# sc16is752.net
KiCad netlist of a schematic drawn in Altium Designer
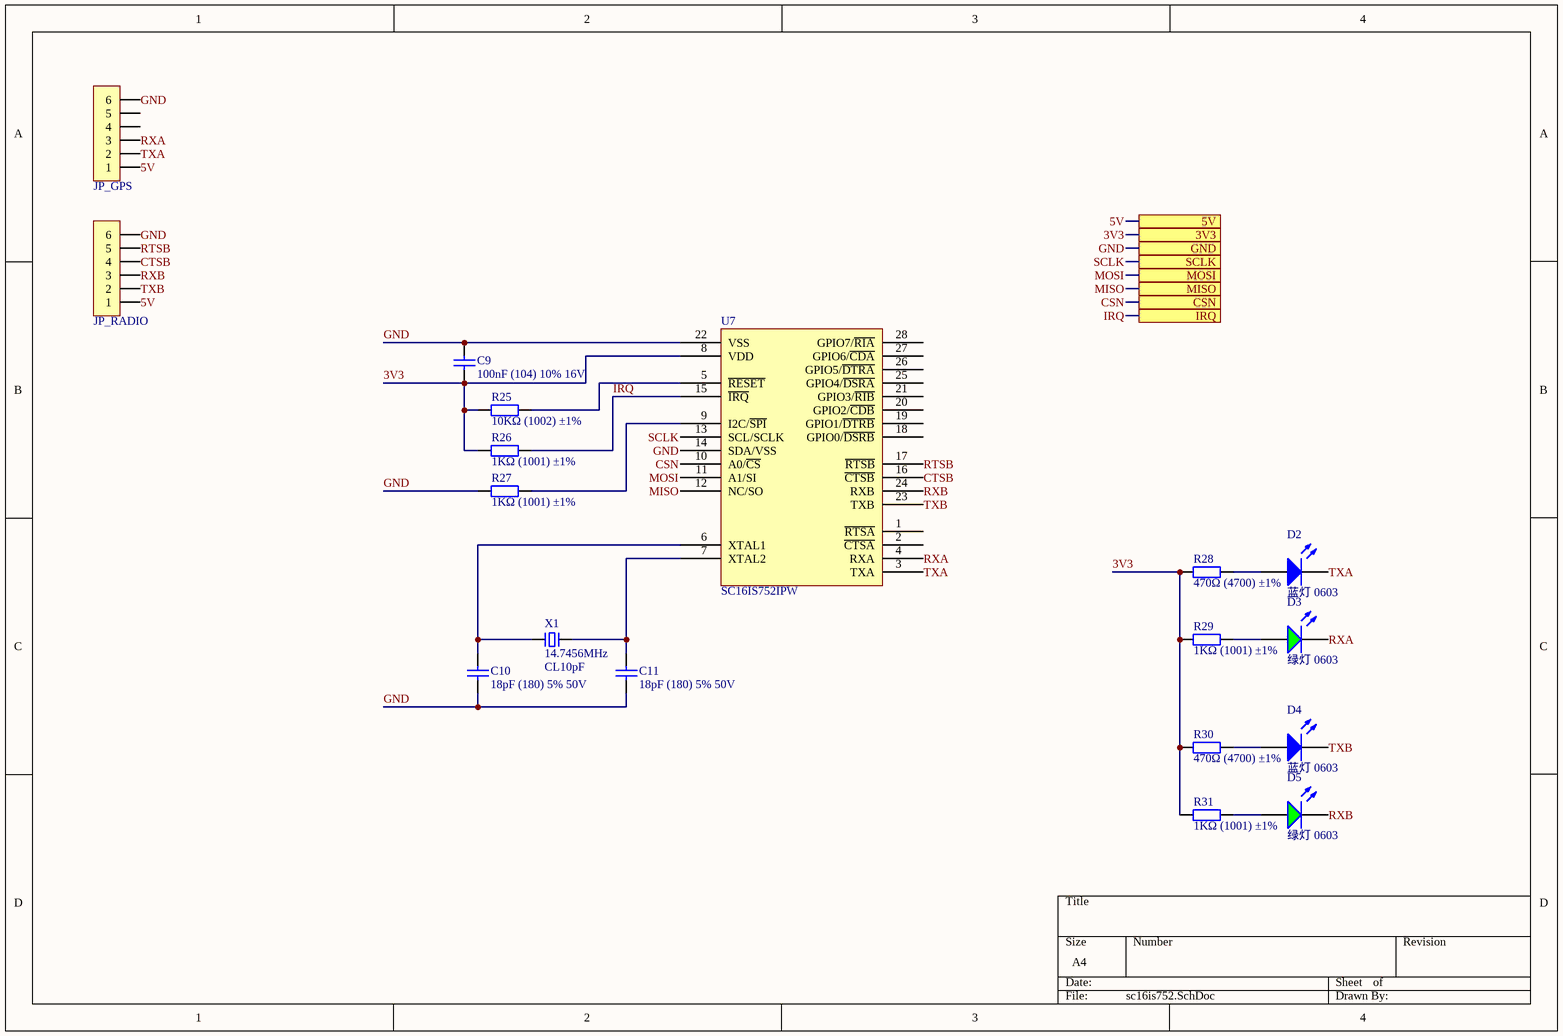
[diagram p0: sc16is752.SchDoc]

(export (version "E")
  (design (tool "Eeschema 10.0.6"))
  (components
    (comp (ref "C9")
      (value "100nF (104) 10% 16V")
      (footprint "0402_C")
      (description "贴片电容")
      (libsource (lib "Miscellaneous Devices LC") (part "0402 100nF (104) 10% 16V"))
    )
    (comp (ref "C10")
      (value "18pF (180) 5% 50V")
      (footprint "0402_C")
      (description "贴片电容")
      (libsource (lib "Miscellaneous Devices LC") (part "0402 18pF (180) 5% 50V"))
    )
    (comp (ref "C11")
      (value "18pF (180) 5% 50V")
      (footprint "0402_C")
      (description "贴片电容")
      (libsource (lib "Miscellaneous Devices LC") (part "0402 18pF (180) 5% 50V"))
    )
    (comp (ref "D2")
      (value "蓝灯 0603")
      (footprint "0603_LED_S1")
      (description "发光二极管")
      (libsource (lib "Miscellaneous Devices LC") (part "0603 蓝灯"))
    )
    (comp (ref "D3")
      (value "绿灯 0603")
      (footprint "0603_LED_S1")
      (description "发光二极管")
      (libsource (lib "Miscellaneous Devices LC") (part "0603 绿灯"))
    )
    (comp (ref "D4")
      (value "蓝灯 0603")
      (footprint "0603_LED_S1")
      (description "发光二极管")
      (libsource (lib "Miscellaneous Devices LC") (part "0603 蓝灯"))
    )
    (comp (ref "D5")
      (value "绿灯 0603")
      (footprint "0603_LED_S1")
      (description "发光二极管")
      (libsource (lib "Miscellaneous Devices LC") (part "0603 绿灯"))
    )
    (comp (ref "JP_GPS")
      (value "HDR-1X6")
      (footprint "MX 1.25-WS-6P")
      (description "6P接插件")
      (fields (field (name "版权归属") "源创客"))
      (libsource (lib "4.2   - 接插件-脚距1.25") (part "Header 6"))
    )
    (comp (ref "JP_RADIO")
      (value "HDR-1X6")
      (footprint "MX 1.25-WS-6P")
      (description "6P接插件")
      (fields (field (name "版权归属") "源创客"))
      (libsource (lib "4.2   - 接插件-脚距1.25") (part "Header 6"))
    )
    (comp (ref "R25")
      (value "10KΩ (1002) ±1%")
      (footprint "0402_R")
      (description "贴片电阻")
      (libsource (lib "Miscellaneous Devices LC") (part "0402 10KΩ (1002) 1%"))
    )
    (comp (ref "R26")
      (value "1KΩ (1001) ±1%")
      (footprint "0402_R")
      (description "贴片电阻")
      (libsource (lib "Miscellaneous Devices LC") (part "0402 1KΩ (1001) 1%"))
    )
    (comp (ref "R27")
      (value "1KΩ (1001) ±1%")
      (footprint "0402_R")
      (description "贴片电阻")
      (libsource (lib "Miscellaneous Devices LC") (part "0402 1KΩ (1001) 1%"))
    )
    (comp (ref "R28")
      (value "470Ω (4700) ±1%")
      (footprint "0402_R")
      (description "贴片电阻")
      (libsource (lib "Miscellaneous Devices LC") (part "0402 470Ω (4700) 1%"))
    )
    (comp (ref "R29")
      (value "1KΩ (1001) ±1%")
      (footprint "0402_R")
      (description "贴片电阻")
      (libsource (lib "Miscellaneous Devices LC") (part "0402 1KΩ (1001) 1%"))
    )
    (comp (ref "R30")
      (value "470Ω (4700) ±1%")
      (footprint "0402_R")
      (description "贴片电阻")
      (libsource (lib "Miscellaneous Devices LC") (part "0402 470Ω (4700) 1%"))
    )
    (comp (ref "R31")
      (value "1KΩ (1001) ±1%")
      (footprint "0402_R")
      (description "贴片电阻")
      (libsource (lib "Miscellaneous Devices LC") (part "0402 1KΩ (1001) 1%"))
    )
    (comp (ref "U7")
      (value "SC16IS752IPW")
      (footprint "TSSOP28_n")
      (libsource (lib "SC16IS752_SC16IS762") (part "SC16IS752IPW"))
    )
    (comp (ref "X1")
      (value "14.7456MHz")
      (footprint "OSC HC-49SMD")
      (description "2脚无源脚晶振")
      (fields (field (name "负载电容") "CL10pF") (field (name "版权归属") "源创客"))
      (libsource (lib "10.1 - 保险丝-晶振") (part "XTAL-2P"))
    )
  )
  (nets
    (net (code "1") (name "/3V3") (class "Default")
      (node (ref "C9") (pin "1") (pinfunction "1_1") (pintype "passive"))
      (node (ref "R25") (pin "1") (pinfunction "1_1") (pintype "passive"))
      (node (ref "R26") (pin "1") (pinfunction "1_1") (pintype "passive"))
      (node (ref "R28") (pin "1") (pinfunction "1_1") (pintype "passive"))
      (node (ref "R29") (pin "1") (pinfunction "1_1") (pintype "passive"))
      (node (ref "R30") (pin "1") (pinfunction "1_1") (pintype "passive"))
      (node (ref "R31") (pin "1") (pinfunction "1_1") (pintype "passive"))
      (node (ref "U7") (pin "8") (pinfunction "VDD_8") (pintype "passive"))
    )
    (net (code "2") (name "/5V") (class "Default")
      (node (ref "JP_GPS") (pin "1") (pinfunction "1_1") (pintype "passive"))
      (node (ref "JP_RADIO") (pin "1") (pinfunction "1_1") (pintype "passive"))
    )
    (net (code "3") (name "/CSN") (class "Default")
      (node (ref "U7") (pin "10") (pinfunction "A0/~{CS}_10") (pintype "passive"))
    )
    (net (code "4") (name "/CTSB") (class "Default")
      (node (ref "JP_RADIO") (pin "4") (pinfunction "4_4") (pintype "passive"))
      (node (ref "U7") (pin "16") (pinfunction "~{CTSB}_16") (pintype "passive"))
    )
    (net (code "5") (name "/GND") (class "Default")
      (node (ref "C10") (pin "1") (pinfunction "1_1") (pintype "passive"))
      (node (ref "C11") (pin "1") (pinfunction "1_1") (pintype "passive"))
      (node (ref "C9") (pin "2") (pinfunction "2_2") (pintype "passive"))
      (node (ref "JP_GPS") (pin "6") (pinfunction "6_6") (pintype "passive"))
      (node (ref "JP_RADIO") (pin "6") (pinfunction "6_6") (pintype "passive"))
      (node (ref "R27") (pin "1") (pinfunction "1_1") (pintype "passive"))
      (node (ref "U7") (pin "14") (pinfunction "SDA/VSS_14") (pintype "passive"))
      (node (ref "U7") (pin "22") (pinfunction "VSS_22") (pintype "passive"))
    )
    (net (code "6") (name "/IRQ") (class "Default")
      (node (ref "R26") (pin "2") (pinfunction "2_2") (pintype "passive"))
      (node (ref "U7") (pin "15") (pinfunction "~{IRQ}_15") (pintype "passive"))
    )
    (net (code "7") (name "/MISO") (class "Default")
      (node (ref "U7") (pin "12") (pinfunction "NC/SO_12") (pintype "passive"))
    )
    (net (code "8") (name "/MOSI") (class "Default")
      (node (ref "U7") (pin "11") (pinfunction "A1/SI_11") (pintype "passive"))
    )
    (net (code "9") (name "/RTSB") (class "Default")
      (node (ref "JP_RADIO") (pin "5") (pinfunction "5_5") (pintype "passive"))
      (node (ref "U7") (pin "17") (pinfunction "~{RTSB}_17") (pintype "passive"))
    )
    (net (code "10") (name "/RXA") (class "Default")
      (node (ref "D3") (pin "K") (pinfunction "K_K") (pintype "passive"))
      (node (ref "JP_GPS") (pin "3") (pinfunction "3_3") (pintype "passive"))
      (node (ref "U7") (pin "4") (pinfunction "RXA_4") (pintype "passive"))
    )
    (net (code "11") (name "/RXB") (class "Default")
      (node (ref "D5") (pin "K") (pinfunction "K_K") (pintype "passive"))
      (node (ref "JP_RADIO") (pin "3") (pinfunction "3_3") (pintype "passive"))
      (node (ref "U7") (pin "24") (pinfunction "RXB_24") (pintype "passive"))
    )
    (net (code "12") (name "/SCLK") (class "Default")
      (node (ref "U7") (pin "13") (pinfunction "SCL/SCLK_13") (pintype "passive"))
    )
    (net (code "13") (name "/TXA") (class "Default")
      (node (ref "D2") (pin "K") (pinfunction "K_K") (pintype "passive"))
      (node (ref "JP_GPS") (pin "2") (pinfunction "2_2") (pintype "passive"))
      (node (ref "U7") (pin "3") (pinfunction "TXA_3") (pintype "passive"))
    )
    (net (code "14") (name "/TXB") (class "Default")
      (node (ref "D4") (pin "K") (pinfunction "K_K") (pintype "passive"))
      (node (ref "JP_RADIO") (pin "2") (pinfunction "2_2") (pintype "passive"))
      (node (ref "U7") (pin "23") (pinfunction "TXB_23") (pintype "passive"))
    )
    (net (code "15") (name "Net-(D2-PadA)") (class "Default")
      (node (ref "D2") (pin "A") (pinfunction "A_A") (pintype "passive"))
      (node (ref "R28") (pin "2") (pinfunction "2_2") (pintype "passive"))
    )
    (net (code "16") (name "Net-(D3-PadA)") (class "Default")
      (node (ref "D3") (pin "A") (pinfunction "A_A") (pintype "passive"))
      (node (ref "R29") (pin "2") (pinfunction "2_2") (pintype "passive"))
    )
    (net (code "17") (name "Net-(D4-PadA)") (class "Default")
      (node (ref "D4") (pin "A") (pinfunction "A_A") (pintype "passive"))
      (node (ref "R30") (pin "2") (pinfunction "2_2") (pintype "passive"))
    )
    (net (code "18") (name "Net-(D5-PadA)") (class "Default")
      (node (ref "D5") (pin "A") (pinfunction "A_A") (pintype "passive"))
      (node (ref "R31") (pin "2") (pinfunction "2_2") (pintype "passive"))
    )
    (net (code "19") (name "Net-(U7-I2C{slash}~{SPI})") (class "Default")
      (node (ref "R27") (pin "2") (pinfunction "2_2") (pintype "passive"))
      (node (ref "U7") (pin "9") (pinfunction "I2C/~{SPI}_9") (pintype "passive"))
    )
    (net (code "20") (name "Net-(U7-XTAL1)") (class "Default")
      (node (ref "C10") (pin "2") (pinfunction "2_2") (pintype "passive"))
      (node (ref "U7") (pin "6") (pinfunction "XTAL1_6") (pintype "passive"))
      (node (ref "X1") (pin "1") (pinfunction "1_1") (pintype "passive"))
    )
    (net (code "21") (name "Net-(U7-XTAL2)") (class "Default")
      (node (ref "C11") (pin "2") (pinfunction "2_2") (pintype "passive"))
      (node (ref "U7") (pin "7") (pinfunction "XTAL2_7") (pintype "passive"))
      (node (ref "X1") (pin "2") (pinfunction "2_2") (pintype "passive"))
    )
    (net (code "22") (name "Net-(U7-~{RESET})") (class "Default")
      (node (ref "R25") (pin "2") (pinfunction "2_2") (pintype "passive"))
      (node (ref "U7") (pin "5") (pinfunction "~{RESET}_5") (pintype "passive"))
    )
    (net (code "23") (name "unconnected-(JP_GPS-Pad4)") (class "Default")
      (node (ref "JP_GPS") (pin "4") (pinfunction "4_4") (pintype "passive"))
    )
    (net (code "24") (name "unconnected-(JP_GPS-Pad5)") (class "Default")
      (node (ref "JP_GPS") (pin "5") (pinfunction "5_5") (pintype "passive"))
    )
    (net (code "25") (name "unconnected-(U7-GPIO0{slash}~{DSRB}-Pad18)") (class "Default")
      (node (ref "U7") (pin "18") (pinfunction "GPIO0/~{DSRB}_18") (pintype "passive"))
    )
    (net (code "26") (name "unconnected-(U7-GPIO1{slash}~{DTRB}-Pad19)") (class "Default")
      (node (ref "U7") (pin "19") (pinfunction "GPIO1/~{DTRB}_19") (pintype "passive"))
    )
    (net (code "27") (name "unconnected-(U7-GPIO2{slash}~{CDB}-Pad20)") (class "Default")
      (node (ref "U7") (pin "20") (pinfunction "GPIO2/~{CDB}_20") (pintype "passive"))
    )
    (net (code "28") (name "unconnected-(U7-GPIO3{slash}~{RIB}-Pad21)") (class "Default")
      (node (ref "U7") (pin "21") (pinfunction "GPIO3/~{RIB}_21") (pintype "passive"))
    )
    (net (code "29") (name "unconnected-(U7-GPIO4{slash}~{DSRA}-Pad25)") (class "Default")
      (node (ref "U7") (pin "25") (pinfunction "GPIO4/~{DSRA}_25") (pintype "passive"))
    )
    (net (code "30") (name "unconnected-(U7-GPIO5{slash}~{DTRA}-Pad26)") (class "Default")
      (node (ref "U7") (pin "26") (pinfunction "GPIO5/~{DTRA}_26") (pintype "passive"))
    )
    (net (code "31") (name "unconnected-(U7-GPIO6{slash}~{CDA}-Pad27)") (class "Default")
      (node (ref "U7") (pin "27") (pinfunction "GPIO6/~{CDA}_27") (pintype "passive"))
    )
    (net (code "32") (name "unconnected-(U7-GPIO7{slash}~{RIA}-Pad28)") (class "Default")
      (node (ref "U7") (pin "28") (pinfunction "GPIO7/~{RIA}_28") (pintype "passive"))
    )
    (net (code "33") (name "unconnected-(U7-~{CTSA}-Pad2)") (class "Default")
      (node (ref "U7") (pin "2") (pinfunction "~{CTSA}_2") (pintype "passive"))
    )
    (net (code "34") (name "unconnected-(U7-~{RTSA}-Pad1)") (class "Default")
      (node (ref "U7") (pin "1") (pinfunction "~{RTSA}_1") (pintype "passive"))
    )
  )
)
